# UFL.net
KiCad netlist of a schematic drawn in Altium Designer
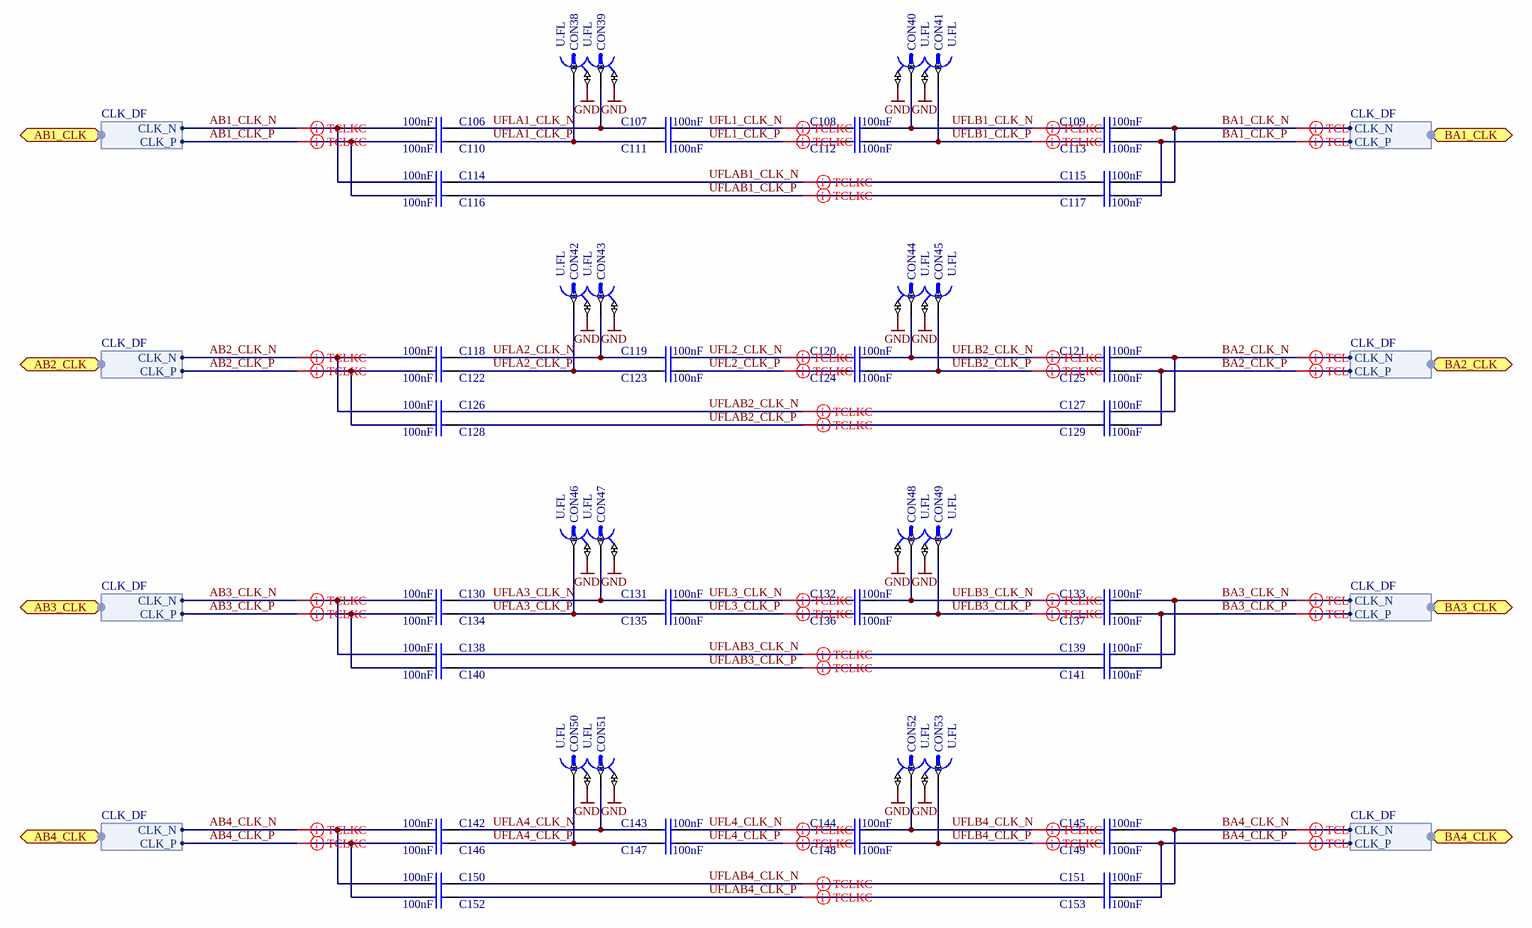
[diagram p0: UFL.SchDoc]

(export (version "E")
  (design (tool "Eeschema 10.0.6"))
  (components
    (comp (ref "C106")
      (value "100nF")
      (footprint "CAPC0603X33N")
      (description "Non-polarised capacitor")
      (fields
        (field (name "PART NUMBER") "CC0201_100NF_6.3V_10%_X5R")
        (field (name "VOLTAGE") "6.3V")
        (field (name "AUTHOR") "CERN DEM JLC")
      )
      (libsource (lib "Capacitors") (part "Capacitor - non polarized"))
    )
    (comp (ref "C107")
      (value "100nF")
      (footprint "CAPC0603X33N")
      (description "Non-polarised capacitor")
      (fields
        (field (name "PART NUMBER") "CC0201_100NF_6.3V_10%_X5R")
        (field (name "VOLTAGE") "6.3V")
        (field (name "AUTHOR") "CERN DEM JLC")
      )
      (libsource (lib "Capacitors") (part "Capacitor - non polarized"))
    )
    (comp (ref "C108")
      (value "100nF")
      (footprint "CAPC0603X33N")
      (description "Non-polarised capacitor")
      (fields
        (field (name "PART NUMBER") "CC0201_100NF_6.3V_10%_X5R")
        (field (name "VOLTAGE") "6.3V")
        (field (name "AUTHOR") "CERN DEM JLC")
      )
      (libsource (lib "Capacitors") (part "Capacitor - non polarized"))
    )
    (comp (ref "C109")
      (value "100nF")
      (footprint "CAPC0603X33N")
      (description "Non-polarised capacitor")
      (fields
        (field (name "PART NUMBER") "CC0201_100NF_6.3V_10%_X5R")
        (field (name "VOLTAGE") "6.3V")
        (field (name "AUTHOR") "CERN DEM JLC")
      )
      (libsource (lib "Capacitors") (part "Capacitor - non polarized"))
    )
    (comp (ref "C110")
      (value "100nF")
      (footprint "CAPC0603X33N")
      (description "Non-polarised capacitor")
      (fields
        (field (name "PART NUMBER") "CC0201_100NF_6.3V_10%_X5R")
        (field (name "VOLTAGE") "6.3V")
        (field (name "AUTHOR") "CERN DEM JLC")
      )
      (libsource (lib "Capacitors") (part "Capacitor - non polarized"))
    )
    (comp (ref "C111")
      (value "100nF")
      (footprint "CAPC0603X33N")
      (description "Non-polarised capacitor")
      (fields
        (field (name "PART NUMBER") "CC0201_100NF_6.3V_10%_X5R")
        (field (name "VOLTAGE") "6.3V")
        (field (name "AUTHOR") "CERN DEM JLC")
      )
      (libsource (lib "Capacitors") (part "Capacitor - non polarized"))
    )
    (comp (ref "C112")
      (value "100nF")
      (footprint "CAPC0603X33N")
      (description "Non-polarised capacitor")
      (fields
        (field (name "PART NUMBER") "CC0201_100NF_6.3V_10%_X5R")
        (field (name "VOLTAGE") "6.3V")
        (field (name "AUTHOR") "CERN DEM JLC")
      )
      (libsource (lib "Capacitors") (part "Capacitor - non polarized"))
    )
    (comp (ref "C113")
      (value "100nF")
      (footprint "CAPC0603X33N")
      (description "Non-polarised capacitor")
      (fields
        (field (name "PART NUMBER") "CC0201_100NF_6.3V_10%_X5R")
        (field (name "VOLTAGE") "6.3V")
        (field (name "AUTHOR") "CERN DEM JLC")
      )
      (libsource (lib "Capacitors") (part "Capacitor - non polarized"))
    )
    (comp (ref "C114")
      (value "100nF")
      (footprint "CAPC0603X33N")
      (description "Non-polarised capacitor")
      (fields
        (field (name "PART NUMBER") "CC0201_100NF_6.3V_10%_X5R")
        (field (name "VOLTAGE") "6.3V")
        (field (name "AUTHOR") "CERN DEM JLC")
      )
      (libsource (lib "Capacitors") (part "Capacitor - non polarized"))
    )
    (comp (ref "C115")
      (value "100nF")
      (footprint "CAPC0603X33N")
      (description "Non-polarised capacitor")
      (fields
        (field (name "PART NUMBER") "CC0201_100NF_6.3V_10%_X5R")
        (field (name "VOLTAGE") "6.3V")
        (field (name "AUTHOR") "CERN DEM JLC")
      )
      (libsource (lib "Capacitors") (part "Capacitor - non polarized"))
    )
    (comp (ref "C116")
      (value "100nF")
      (footprint "CAPC0603X33N")
      (description "Non-polarised capacitor")
      (fields
        (field (name "PART NUMBER") "CC0201_100NF_6.3V_10%_X5R")
        (field (name "VOLTAGE") "6.3V")
        (field (name "AUTHOR") "CERN DEM JLC")
      )
      (libsource (lib "Capacitors") (part "Capacitor - non polarized"))
    )
    (comp (ref "C117")
      (value "100nF")
      (footprint "CAPC0603X33N")
      (description "Non-polarised capacitor")
      (fields
        (field (name "PART NUMBER") "CC0201_100NF_6.3V_10%_X5R")
        (field (name "VOLTAGE") "6.3V")
        (field (name "AUTHOR") "CERN DEM JLC")
      )
      (libsource (lib "Capacitors") (part "Capacitor - non polarized"))
    )
    (comp (ref "C118")
      (value "100nF")
      (footprint "CAPC0603X33N")
      (description "Non-polarised capacitor")
      (fields
        (field (name "PART NUMBER") "CC0201_100NF_6.3V_10%_X5R")
        (field (name "VOLTAGE") "6.3V")
        (field (name "AUTHOR") "CERN DEM JLC")
      )
      (libsource (lib "Capacitors") (part "Capacitor - non polarized"))
    )
    (comp (ref "C119")
      (value "100nF")
      (footprint "CAPC0603X33N")
      (description "Non-polarised capacitor")
      (fields
        (field (name "PART NUMBER") "CC0201_100NF_6.3V_10%_X5R")
        (field (name "VOLTAGE") "6.3V")
        (field (name "AUTHOR") "CERN DEM JLC")
      )
      (libsource (lib "Capacitors") (part "Capacitor - non polarized"))
    )
    (comp (ref "C120")
      (value "100nF")
      (footprint "CAPC0603X33N")
      (description "Non-polarised capacitor")
      (fields
        (field (name "PART NUMBER") "CC0201_100NF_6.3V_10%_X5R")
        (field (name "VOLTAGE") "6.3V")
        (field (name "AUTHOR") "CERN DEM JLC")
      )
      (libsource (lib "Capacitors") (part "Capacitor - non polarized"))
    )
    (comp (ref "C121")
      (value "100nF")
      (footprint "CAPC0603X33N")
      (description "Non-polarised capacitor")
      (fields
        (field (name "PART NUMBER") "CC0201_100NF_6.3V_10%_X5R")
        (field (name "VOLTAGE") "6.3V")
        (field (name "AUTHOR") "CERN DEM JLC")
      )
      (libsource (lib "Capacitors") (part "Capacitor - non polarized"))
    )
    (comp (ref "C122")
      (value "100nF")
      (footprint "CAPC0603X33N")
      (description "Non-polarised capacitor")
      (fields
        (field (name "PART NUMBER") "CC0201_100NF_6.3V_10%_X5R")
        (field (name "VOLTAGE") "6.3V")
        (field (name "AUTHOR") "CERN DEM JLC")
      )
      (libsource (lib "Capacitors") (part "Capacitor - non polarized"))
    )
    (comp (ref "C123")
      (value "100nF")
      (footprint "CAPC0603X33N")
      (description "Non-polarised capacitor")
      (fields
        (field (name "PART NUMBER") "CC0201_100NF_6.3V_10%_X5R")
        (field (name "VOLTAGE") "6.3V")
        (field (name "AUTHOR") "CERN DEM JLC")
      )
      (libsource (lib "Capacitors") (part "Capacitor - non polarized"))
    )
    (comp (ref "C124")
      (value "100nF")
      (footprint "CAPC0603X33N")
      (description "Non-polarised capacitor")
      (fields
        (field (name "PART NUMBER") "CC0201_100NF_6.3V_10%_X5R")
        (field (name "VOLTAGE") "6.3V")
        (field (name "AUTHOR") "CERN DEM JLC")
      )
      (libsource (lib "Capacitors") (part "Capacitor - non polarized"))
    )
    (comp (ref "C125")
      (value "100nF")
      (footprint "CAPC0603X33N")
      (description "Non-polarised capacitor")
      (fields
        (field (name "PART NUMBER") "CC0201_100NF_6.3V_10%_X5R")
        (field (name "VOLTAGE") "6.3V")
        (field (name "AUTHOR") "CERN DEM JLC")
      )
      (libsource (lib "Capacitors") (part "Capacitor - non polarized"))
    )
    (comp (ref "C126")
      (value "100nF")
      (footprint "CAPC0603X33N")
      (description "Non-polarised capacitor")
      (fields
        (field (name "PART NUMBER") "CC0201_100NF_6.3V_10%_X5R")
        (field (name "VOLTAGE") "6.3V")
        (field (name "AUTHOR") "CERN DEM JLC")
      )
      (libsource (lib "Capacitors") (part "Capacitor - non polarized"))
    )
    (comp (ref "C127")
      (value "100nF")
      (footprint "CAPC0603X33N")
      (description "Non-polarised capacitor")
      (fields
        (field (name "PART NUMBER") "CC0201_100NF_6.3V_10%_X5R")
        (field (name "VOLTAGE") "6.3V")
        (field (name "AUTHOR") "CERN DEM JLC")
      )
      (libsource (lib "Capacitors") (part "Capacitor - non polarized"))
    )
    (comp (ref "C128")
      (value "100nF")
      (footprint "CAPC0603X33N")
      (description "Non-polarised capacitor")
      (fields
        (field (name "PART NUMBER") "CC0201_100NF_6.3V_10%_X5R")
        (field (name "VOLTAGE") "6.3V")
        (field (name "AUTHOR") "CERN DEM JLC")
      )
      (libsource (lib "Capacitors") (part "Capacitor - non polarized"))
    )
    (comp (ref "C129")
      (value "100nF")
      (footprint "CAPC0603X33N")
      (description "Non-polarised capacitor")
      (fields
        (field (name "PART NUMBER") "CC0201_100NF_6.3V_10%_X5R")
        (field (name "VOLTAGE") "6.3V")
        (field (name "AUTHOR") "CERN DEM JLC")
      )
      (libsource (lib "Capacitors") (part "Capacitor - non polarized"))
    )
    (comp (ref "C130")
      (value "100nF")
      (footprint "CAPC0603X33N")
      (description "Non-polarised capacitor")
      (fields
        (field (name "PART NUMBER") "CC0201_100NF_6.3V_10%_X5R")
        (field (name "VOLTAGE") "6.3V")
        (field (name "AUTHOR") "CERN DEM JLC")
      )
      (libsource (lib "Capacitors") (part "Capacitor - non polarized"))
    )
    (comp (ref "C131")
      (value "100nF")
      (footprint "CAPC0603X33N")
      (description "Non-polarised capacitor")
      (fields
        (field (name "PART NUMBER") "CC0201_100NF_6.3V_10%_X5R")
        (field (name "VOLTAGE") "6.3V")
        (field (name "AUTHOR") "CERN DEM JLC")
      )
      (libsource (lib "Capacitors") (part "Capacitor - non polarized"))
    )
    (comp (ref "C132")
      (value "100nF")
      (footprint "CAPC0603X33N")
      (description "Non-polarised capacitor")
      (fields
        (field (name "PART NUMBER") "CC0201_100NF_6.3V_10%_X5R")
        (field (name "VOLTAGE") "6.3V")
        (field (name "AUTHOR") "CERN DEM JLC")
      )
      (libsource (lib "Capacitors") (part "Capacitor - non polarized"))
    )
    (comp (ref "C133")
      (value "100nF")
      (footprint "CAPC0603X33N")
      (description "Non-polarised capacitor")
      (fields
        (field (name "PART NUMBER") "CC0201_100NF_6.3V_10%_X5R")
        (field (name "VOLTAGE") "6.3V")
        (field (name "AUTHOR") "CERN DEM JLC")
      )
      (libsource (lib "Capacitors") (part "Capacitor - non polarized"))
    )
    (comp (ref "C134")
      (value "100nF")
      (footprint "CAPC0603X33N")
      (description "Non-polarised capacitor")
      (fields
        (field (name "PART NUMBER") "CC0201_100NF_6.3V_10%_X5R")
        (field (name "VOLTAGE") "6.3V")
        (field (name "AUTHOR") "CERN DEM JLC")
      )
      (libsource (lib "Capacitors") (part "Capacitor - non polarized"))
    )
    (comp (ref "C135")
      (value "100nF")
      (footprint "CAPC0603X33N")
      (description "Non-polarised capacitor")
      (fields
        (field (name "PART NUMBER") "CC0201_100NF_6.3V_10%_X5R")
        (field (name "VOLTAGE") "6.3V")
        (field (name "AUTHOR") "CERN DEM JLC")
      )
      (libsource (lib "Capacitors") (part "Capacitor - non polarized"))
    )
    (comp (ref "C136")
      (value "100nF")
      (footprint "CAPC0603X33N")
      (description "Non-polarised capacitor")
      (fields
        (field (name "PART NUMBER") "CC0201_100NF_6.3V_10%_X5R")
        (field (name "VOLTAGE") "6.3V")
        (field (name "AUTHOR") "CERN DEM JLC")
      )
      (libsource (lib "Capacitors") (part "Capacitor - non polarized"))
    )
    (comp (ref "C137")
      (value "100nF")
      (footprint "CAPC0603X33N")
      (description "Non-polarised capacitor")
      (fields
        (field (name "PART NUMBER") "CC0201_100NF_6.3V_10%_X5R")
        (field (name "VOLTAGE") "6.3V")
        (field (name "AUTHOR") "CERN DEM JLC")
      )
      (libsource (lib "Capacitors") (part "Capacitor - non polarized"))
    )
    (comp (ref "C138")
      (value "100nF")
      (footprint "CAPC0603X33N")
      (description "Non-polarised capacitor")
      (fields
        (field (name "PART NUMBER") "CC0201_100NF_6.3V_10%_X5R")
        (field (name "VOLTAGE") "6.3V")
        (field (name "AUTHOR") "CERN DEM JLC")
      )
      (libsource (lib "Capacitors") (part "Capacitor - non polarized"))
    )
    (comp (ref "C139")
      (value "100nF")
      (footprint "CAPC0603X33N")
      (description "Non-polarised capacitor")
      (fields
        (field (name "PART NUMBER") "CC0201_100NF_6.3V_10%_X5R")
        (field (name "VOLTAGE") "6.3V")
        (field (name "AUTHOR") "CERN DEM JLC")
      )
      (libsource (lib "Capacitors") (part "Capacitor - non polarized"))
    )
    (comp (ref "C140")
      (value "100nF")
      (footprint "CAPC0603X33N")
      (description "Non-polarised capacitor")
      (fields
        (field (name "PART NUMBER") "CC0201_100NF_6.3V_10%_X5R")
        (field (name "VOLTAGE") "6.3V")
        (field (name "AUTHOR") "CERN DEM JLC")
      )
      (libsource (lib "Capacitors") (part "Capacitor - non polarized"))
    )
    (comp (ref "C141")
      (value "100nF")
      (footprint "CAPC0603X33N")
      (description "Non-polarised capacitor")
      (fields
        (field (name "PART NUMBER") "CC0201_100NF_6.3V_10%_X5R")
        (field (name "VOLTAGE") "6.3V")
        (field (name "AUTHOR") "CERN DEM JLC")
      )
      (libsource (lib "Capacitors") (part "Capacitor - non polarized"))
    )
    (comp (ref "C142")
      (value "100nF")
      (footprint "CAPC0603X33N")
      (description "Non-polarised capacitor")
      (fields
        (field (name "PART NUMBER") "CC0201_100NF_6.3V_10%_X5R")
        (field (name "VOLTAGE") "6.3V")
        (field (name "AUTHOR") "CERN DEM JLC")
      )
      (libsource (lib "Capacitors") (part "Capacitor - non polarized"))
    )
    (comp (ref "C143")
      (value "100nF")
      (footprint "CAPC0603X33N")
      (description "Non-polarised capacitor")
      (fields
        (field (name "PART NUMBER") "CC0201_100NF_6.3V_10%_X5R")
        (field (name "VOLTAGE") "6.3V")
        (field (name "AUTHOR") "CERN DEM JLC")
      )
      (libsource (lib "Capacitors") (part "Capacitor - non polarized"))
    )
    (comp (ref "C144")
      (value "100nF")
      (footprint "CAPC0603X33N")
      (description "Non-polarised capacitor")
      (fields
        (field (name "PART NUMBER") "CC0201_100NF_6.3V_10%_X5R")
        (field (name "VOLTAGE") "6.3V")
        (field (name "AUTHOR") "CERN DEM JLC")
      )
      (libsource (lib "Capacitors") (part "Capacitor - non polarized"))
    )
    (comp (ref "C145")
      (value "100nF")
      (footprint "CAPC0603X33N")
      (description "Non-polarised capacitor")
      (fields
        (field (name "PART NUMBER") "CC0201_100NF_6.3V_10%_X5R")
        (field (name "VOLTAGE") "6.3V")
        (field (name "AUTHOR") "CERN DEM JLC")
      )
      (libsource (lib "Capacitors") (part "Capacitor - non polarized"))
    )
    (comp (ref "C146")
      (value "100nF")
      (footprint "CAPC0603X33N")
      (description "Non-polarised capacitor")
      (fields
        (field (name "PART NUMBER") "CC0201_100NF_6.3V_10%_X5R")
        (field (name "VOLTAGE") "6.3V")
        (field (name "AUTHOR") "CERN DEM JLC")
      )
      (libsource (lib "Capacitors") (part "Capacitor - non polarized"))
    )
    (comp (ref "C147")
      (value "100nF")
      (footprint "CAPC0603X33N")
      (description "Non-polarised capacitor")
      (fields
        (field (name "PART NUMBER") "CC0201_100NF_6.3V_10%_X5R")
        (field (name "VOLTAGE") "6.3V")
        (field (name "AUTHOR") "CERN DEM JLC")
      )
      (libsource (lib "Capacitors") (part "Capacitor - non polarized"))
    )
    (comp (ref "C148")
      (value "100nF")
      (footprint "CAPC0603X33N")
      (description "Non-polarised capacitor")
      (fields
        (field (name "PART NUMBER") "CC0201_100NF_6.3V_10%_X5R")
        (field (name "VOLTAGE") "6.3V")
        (field (name "AUTHOR") "CERN DEM JLC")
      )
      (libsource (lib "Capacitors") (part "Capacitor - non polarized"))
    )
    (comp (ref "C149")
      (value "100nF")
      (footprint "CAPC0603X33N")
      (description "Non-polarised capacitor")
      (fields
        (field (name "PART NUMBER") "CC0201_100NF_6.3V_10%_X5R")
        (field (name "VOLTAGE") "6.3V")
        (field (name "AUTHOR") "CERN DEM JLC")
      )
      (libsource (lib "Capacitors") (part "Capacitor - non polarized"))
    )
    (comp (ref "C150")
      (value "100nF")
      (footprint "CAPC0603X33N")
      (description "Non-polarised capacitor")
      (fields
        (field (name "PART NUMBER") "CC0201_100NF_6.3V_10%_X5R")
        (field (name "VOLTAGE") "6.3V")
        (field (name "AUTHOR") "CERN DEM JLC")
      )
      (libsource (lib "Capacitors") (part "Capacitor - non polarized"))
    )
    (comp (ref "C151")
      (value "100nF")
      (footprint "CAPC0603X33N")
      (description "Non-polarised capacitor")
      (fields
        (field (name "PART NUMBER") "CC0201_100NF_6.3V_10%_X5R")
        (field (name "VOLTAGE") "6.3V")
        (field (name "AUTHOR") "CERN DEM JLC")
      )
      (libsource (lib "Capacitors") (part "Capacitor - non polarized"))
    )
    (comp (ref "C152")
      (value "100nF")
      (footprint "CAPC0603X33N")
      (description "Non-polarised capacitor")
      (fields
        (field (name "PART NUMBER") "CC0201_100NF_6.3V_10%_X5R")
        (field (name "VOLTAGE") "6.3V")
        (field (name "AUTHOR") "CERN DEM JLC")
      )
      (libsource (lib "Capacitors") (part "Capacitor - non polarized"))
    )
    (comp (ref "C153")
      (value "100nF")
      (footprint "CAPC0603X33N")
      (description "Non-polarised capacitor")
      (fields
        (field (name "PART NUMBER") "CC0201_100NF_6.3V_10%_X5R")
        (field (name "VOLTAGE") "6.3V")
        (field (name "AUTHOR") "CERN DEM JLC")
      )
      (libsource (lib "Capacitors") (part "Capacitor - non polarized"))
    )
    (comp (ref "CON38")
      (value "U.FL")
      (footprint "HIROSE_U.FL-R-SMT-1(10)")
      (fields
        (field (name "PART NUMBER") "HIROSE_U.FL-R-SMT-1(10)")
        (field (name "MANUFACTURER") "HIROSE (HRS)")
        (field (name "MANUFACTURER PART NUMBER") "U.FL-R-SMT-1(10)")
        (field (name "AUTHOR") "CERN DEM JLC")
      )
      (libsource (lib "Connectors") (part "Coax_1Male_1Shield"))
    )
    (comp (ref "CON39")
      (value "U.FL")
      (footprint "HIROSE_U.FL-R-SMT-1(10)")
      (fields
        (field (name "PART NUMBER") "HIROSE_U.FL-R-SMT-1(10)")
        (field (name "MANUFACTURER") "HIROSE (HRS)")
        (field (name "MANUFACTURER PART NUMBER") "U.FL-R-SMT-1(10)")
        (field (name "AUTHOR") "CERN DEM JLC")
      )
      (libsource (lib "Connectors") (part "Coax_1Male_1Shield"))
    )
    (comp (ref "CON40")
      (value "U.FL")
      (footprint "HIROSE_U.FL-R-SMT-1(10)")
      (fields
        (field (name "PART NUMBER") "HIROSE_U.FL-R-SMT-1(10)")
        (field (name "MANUFACTURER") "HIROSE (HRS)")
        (field (name "MANUFACTURER PART NUMBER") "U.FL-R-SMT-1(10)")
        (field (name "AUTHOR") "CERN DEM JLC")
      )
      (libsource (lib "") (part "Coax_1Male_1Shield_1"))
    )
    (comp (ref "CON41")
      (value "U.FL")
      (footprint "HIROSE_U.FL-R-SMT-1(10)")
      (fields
        (field (name "PART NUMBER") "HIROSE_U.FL-R-SMT-1(10)")
        (field (name "MANUFACTURER") "HIROSE (HRS)")
        (field (name "MANUFACTURER PART NUMBER") "U.FL-R-SMT-1(10)")
        (field (name "AUTHOR") "CERN DEM JLC")
      )
      (libsource (lib "") (part "Coax_1Male_1Shield_1"))
    )
    (comp (ref "CON42")
      (value "U.FL")
      (footprint "HIROSE_U.FL-R-SMT-1(10)")
      (fields
        (field (name "PART NUMBER") "HIROSE_U.FL-R-SMT-1(10)")
        (field (name "MANUFACTURER") "HIROSE (HRS)")
        (field (name "MANUFACTURER PART NUMBER") "U.FL-R-SMT-1(10)")
        (field (name "AUTHOR") "CERN DEM JLC")
      )
      (libsource (lib "Connectors") (part "Coax_1Male_1Shield"))
    )
    (comp (ref "CON43")
      (value "U.FL")
      (footprint "HIROSE_U.FL-R-SMT-1(10)")
      (fields
        (field (name "PART NUMBER") "HIROSE_U.FL-R-SMT-1(10)")
        (field (name "MANUFACTURER") "HIROSE (HRS)")
        (field (name "MANUFACTURER PART NUMBER") "U.FL-R-SMT-1(10)")
        (field (name "AUTHOR") "CERN DEM JLC")
      )
      (libsource (lib "Connectors") (part "Coax_1Male_1Shield"))
    )
    (comp (ref "CON44")
      (value "U.FL")
      (footprint "HIROSE_U.FL-R-SMT-1(10)")
      (fields
        (field (name "PART NUMBER") "HIROSE_U.FL-R-SMT-1(10)")
        (field (name "MANUFACTURER") "HIROSE (HRS)")
        (field (name "MANUFACTURER PART NUMBER") "U.FL-R-SMT-1(10)")
        (field (name "AUTHOR") "CERN DEM JLC")
      )
      (libsource (lib "") (part "Coax_1Male_1Shield_1"))
    )
    (comp (ref "CON45")
      (value "U.FL")
      (footprint "HIROSE_U.FL-R-SMT-1(10)")
      (fields
        (field (name "PART NUMBER") "HIROSE_U.FL-R-SMT-1(10)")
        (field (name "MANUFACTURER") "HIROSE (HRS)")
        (field (name "MANUFACTURER PART NUMBER") "U.FL-R-SMT-1(10)")
        (field (name "AUTHOR") "CERN DEM JLC")
      )
      (libsource (lib "") (part "Coax_1Male_1Shield_1"))
    )
    (comp (ref "CON46")
      (value "U.FL")
      (footprint "HIROSE_U.FL-R-SMT-1(10)")
      (fields
        (field (name "PART NUMBER") "HIROSE_U.FL-R-SMT-1(10)")
        (field (name "MANUFACTURER") "HIROSE (HRS)")
        (field (name "MANUFACTURER PART NUMBER") "U.FL-R-SMT-1(10)")
        (field (name "AUTHOR") "CERN DEM JLC")
      )
      (libsource (lib "Connectors") (part "Coax_1Male_1Shield"))
    )
    (comp (ref "CON47")
      (value "U.FL")
      (footprint "HIROSE_U.FL-R-SMT-1(10)")
      (fields
        (field (name "PART NUMBER") "HIROSE_U.FL-R-SMT-1(10)")
        (field (name "MANUFACTURER") "HIROSE (HRS)")
        (field (name "MANUFACTURER PART NUMBER") "U.FL-R-SMT-1(10)")
        (field (name "AUTHOR") "CERN DEM JLC")
      )
      (libsource (lib "Connectors") (part "Coax_1Male_1Shield"))
    )
    (comp (ref "CON48")
      (value "U.FL")
      (footprint "HIROSE_U.FL-R-SMT-1(10)")
      (fields
        (field (name "PART NUMBER") "HIROSE_U.FL-R-SMT-1(10)")
        (field (name "MANUFACTURER") "HIROSE (HRS)")
        (field (name "MANUFACTURER PART NUMBER") "U.FL-R-SMT-1(10)")
        (field (name "AUTHOR") "CERN DEM JLC")
      )
      (libsource (lib "") (part "Coax_1Male_1Shield_1"))
    )
    (comp (ref "CON49")
      (value "U.FL")
      (footprint "HIROSE_U.FL-R-SMT-1(10)")
      (fields
        (field (name "PART NUMBER") "HIROSE_U.FL-R-SMT-1(10)")
        (field (name "MANUFACTURER") "HIROSE (HRS)")
        (field (name "MANUFACTURER PART NUMBER") "U.FL-R-SMT-1(10)")
        (field (name "AUTHOR") "CERN DEM JLC")
      )
      (libsource (lib "") (part "Coax_1Male_1Shield_1"))
    )
    (comp (ref "CON50")
      (value "U.FL")
      (footprint "HIROSE_U.FL-R-SMT-1(10)")
      (fields
        (field (name "PART NUMBER") "HIROSE_U.FL-R-SMT-1(10)")
        (field (name "MANUFACTURER") "HIROSE (HRS)")
        (field (name "MANUFACTURER PART NUMBER") "U.FL-R-SMT-1(10)")
        (field (name "AUTHOR") "CERN DEM JLC")
      )
      (libsource (lib "Connectors") (part "Coax_1Male_1Shield"))
    )
    (comp (ref "CON51")
      (value "U.FL")
      (footprint "HIROSE_U.FL-R-SMT-1(10)")
      (fields
        (field (name "PART NUMBER") "HIROSE_U.FL-R-SMT-1(10)")
        (field (name "MANUFACTURER") "HIROSE (HRS)")
        (field (name "MANUFACTURER PART NUMBER") "U.FL-R-SMT-1(10)")
        (field (name "AUTHOR") "CERN DEM JLC")
      )
      (libsource (lib "Connectors") (part "Coax_1Male_1Shield"))
    )
    (comp (ref "CON52")
      (value "U.FL")
      (footprint "HIROSE_U.FL-R-SMT-1(10)")
      (fields
        (field (name "PART NUMBER") "HIROSE_U.FL-R-SMT-1(10)")
        (field (name "MANUFACTURER") "HIROSE (HRS)")
        (field (name "MANUFACTURER PART NUMBER") "U.FL-R-SMT-1(10)")
        (field (name "AUTHOR") "CERN DEM JLC")
      )
      (libsource (lib "") (part "Coax_1Male_1Shield_1"))
    )
    (comp (ref "CON53")
      (value "U.FL")
      (footprint "HIROSE_U.FL-R-SMT-1(10)")
      (fields
        (field (name "PART NUMBER") "HIROSE_U.FL-R-SMT-1(10)")
        (field (name "MANUFACTURER") "HIROSE (HRS)")
        (field (name "MANUFACTURER PART NUMBER") "U.FL-R-SMT-1(10)")
        (field (name "AUTHOR") "CERN DEM JLC")
      )
      (libsource (lib "") (part "Coax_1Male_1Shield_1"))
    )
  )
  (nets
    (net (code "2") (name "/AB1_CLK_N") (class "Default")
      (node (ref "C106") (pin "1") (pinfunction "1_1") (pintype "passive"))
      (node (ref "C114") (pin "1") (pinfunction "1_1") (pintype "passive"))
    )
    (net (code "3") (name "/AB1_CLK_P") (class "Default")
      (node (ref "C110") (pin "1") (pinfunction "1_1") (pintype "passive"))
      (node (ref "C116") (pin "1") (pinfunction "1_1") (pintype "passive"))
    )
    (net (code "4") (name "/AB2_CLK_N") (class "Default")
      (node (ref "C118") (pin "1") (pinfunction "1_1") (pintype "passive"))
      (node (ref "C126") (pin "1") (pinfunction "1_1") (pintype "passive"))
    )
    (net (code "5") (name "/AB2_CLK_P") (class "Default")
      (node (ref "C122") (pin "1") (pinfunction "1_1") (pintype "passive"))
      (node (ref "C128") (pin "1") (pinfunction "1_1") (pintype "passive"))
    )
    (net (code "6") (name "/AB3_CLK_N") (class "Default")
      (node (ref "C130") (pin "1") (pinfunction "1_1") (pintype "passive"))
      (node (ref "C138") (pin "1") (pinfunction "1_1") (pintype "passive"))
    )
    (net (code "7") (name "/AB3_CLK_P") (class "Default")
      (node (ref "C134") (pin "1") (pinfunction "1_1") (pintype "passive"))
      (node (ref "C140") (pin "1") (pinfunction "1_1") (pintype "passive"))
    )
    (net (code "8") (name "/AB4_CLK_N") (class "Default")
      (node (ref "C142") (pin "1") (pinfunction "1_1") (pintype "passive"))
      (node (ref "C150") (pin "1") (pinfunction "1_1") (pintype "passive"))
    )
    (net (code "9") (name "/AB4_CLK_P") (class "Default")
      (node (ref "C146") (pin "1") (pinfunction "1_1") (pintype "passive"))
      (node (ref "C152") (pin "1") (pinfunction "1_1") (pintype "passive"))
    )
    (net (code "10") (name "/BA1_CLK_N") (class "Default")
      (node (ref "C109") (pin "1") (pinfunction "1_1") (pintype "passive"))
      (node (ref "C115") (pin "1") (pinfunction "1_1") (pintype "passive"))
    )
    (net (code "11") (name "/BA1_CLK_P") (class "Default")
      (node (ref "C113") (pin "1") (pinfunction "1_1") (pintype "passive"))
      (node (ref "C117") (pin "1") (pinfunction "1_1") (pintype "passive"))
    )
    (net (code "12") (name "/BA2_CLK_N") (class "Default")
      (node (ref "C121") (pin "1") (pinfunction "1_1") (pintype "passive"))
      (node (ref "C127") (pin "1") (pinfunction "1_1") (pintype "passive"))
    )
    (net (code "13") (name "/BA2_CLK_P") (class "Default")
      (node (ref "C125") (pin "1") (pinfunction "1_1") (pintype "passive"))
      (node (ref "C129") (pin "1") (pinfunction "1_1") (pintype "passive"))
    )
    (net (code "14") (name "/BA3_CLK_N") (class "Default")
      (node (ref "C133") (pin "1") (pinfunction "1_1") (pintype "passive"))
      (node (ref "C139") (pin "1") (pinfunction "1_1") (pintype "passive"))
    )
    (net (code "15") (name "/BA3_CLK_P") (class "Default")
      (node (ref "C137") (pin "1") (pinfunction "1_1") (pintype "passive"))
      (node (ref "C141") (pin "1") (pinfunction "1_1") (pintype "passive"))
    )
    (net (code "16") (name "/BA4_CLK_N") (class "Default")
      (node (ref "C145") (pin "1") (pinfunction "1_1") (pintype "passive"))
      (node (ref "C151") (pin "1") (pinfunction "1_1") (pintype "passive"))
    )
    (net (code "17") (name "/BA4_CLK_P") (class "Default")
      (node (ref "C149") (pin "1") (pinfunction "1_1") (pintype "passive"))
      (node (ref "C153") (pin "1") (pinfunction "1_1") (pintype "passive"))
    )
    (net (code "18") (name "/UFL1_CLK_N") (class "Default")
      (node (ref "C107") (pin "1") (pinfunction "1_1") (pintype "passive"))
      (node (ref "C108") (pin "2") (pinfunction "2_2") (pintype "passive"))
    )
    (net (code "19") (name "/UFL1_CLK_P") (class "Default")
      (node (ref "C111") (pin "1") (pinfunction "1_1") (pintype "passive"))
      (node (ref "C112") (pin "2") (pinfunction "2_2") (pintype "passive"))
    )
    (net (code "20") (name "/UFL2_CLK_N") (class "Default")
      (node (ref "C119") (pin "1") (pinfunction "1_1") (pintype "passive"))
      (node (ref "C120") (pin "2") (pinfunction "2_2") (pintype "passive"))
    )
    (net (code "21") (name "/UFL2_CLK_P") (class "Default")
      (node (ref "C123") (pin "1") (pinfunction "1_1") (pintype "passive"))
      (node (ref "C124") (pin "2") (pinfunction "2_2") (pintype "passive"))
    )
    (net (code "22") (name "/UFL3_CLK_N") (class "Default")
      (node (ref "C131") (pin "1") (pinfunction "1_1") (pintype "passive"))
      (node (ref "C132") (pin "2") (pinfunction "2_2") (pintype "passive"))
    )
    (net (code "23") (name "/UFL3_CLK_P") (class "Default")
      (node (ref "C135") (pin "1") (pinfunction "1_1") (pintype "passive"))
      (node (ref "C136") (pin "2") (pinfunction "2_2") (pintype "passive"))
    )
    (net (code "24") (name "/UFL4_CLK_N") (class "Default")
      (node (ref "C143") (pin "1") (pinfunction "1_1") (pintype "passive"))
      (node (ref "C144") (pin "2") (pinfunction "2_2") (pintype "passive"))
    )
    (net (code "25") (name "/UFL4_CLK_P") (class "Default")
      (node (ref "C147") (pin "1") (pinfunction "1_1") (pintype "passive"))
      (node (ref "C148") (pin "2") (pinfunction "2_2") (pintype "passive"))
    )
    (net (code "26") (name "/UFLA1_CLK_N") (class "Default")
      (node (ref "C106") (pin "2") (pinfunction "2_2") (pintype "passive"))
      (node (ref "C107") (pin "2") (pinfunction "2_2") (pintype "passive"))
      (node (ref "CON39") (pin "1") (pinfunction "1_1") (pintype "bidirectional"))
    )
    (net (code "27") (name "/UFLA1_CLK_P") (class "Default")
      (node (ref "C110") (pin "2") (pinfunction "2_2") (pintype "passive"))
      (node (ref "C111") (pin "2") (pinfunction "2_2") (pintype "passive"))
      (node (ref "CON38") (pin "1") (pinfunction "1_1") (pintype "bidirectional"))
    )
    (net (code "28") (name "/UFLA2_CLK_N") (class "Default")
      (node (ref "C118") (pin "2") (pinfunction "2_2") (pintype "passive"))
      (node (ref "C119") (pin "2") (pinfunction "2_2") (pintype "passive"))
      (node (ref "CON43") (pin "1") (pinfunction "1_1") (pintype "bidirectional"))
    )
    (net (code "29") (name "/UFLA2_CLK_P") (class "Default")
      (node (ref "C122") (pin "2") (pinfunction "2_2") (pintype "passive"))
      (node (ref "C123") (pin "2") (pinfunction "2_2") (pintype "passive"))
      (node (ref "CON42") (pin "1") (pinfunction "1_1") (pintype "bidirectional"))
    )
    (net (code "30") (name "/UFLA3_CLK_N") (class "Default")
      (node (ref "C130") (pin "2") (pinfunction "2_2") (pintype "passive"))
      (node (ref "C131") (pin "2") (pinfunction "2_2") (pintype "passive"))
      (node (ref "CON47") (pin "1") (pinfunction "1_1") (pintype "bidirectional"))
    )
    (net (code "31") (name "/UFLA3_CLK_P") (class "Default")
      (node (ref "C134") (pin "2") (pinfunction "2_2") (pintype "passive"))
      (node (ref "C135") (pin "2") (pinfunction "2_2") (pintype "passive"))
      (node (ref "CON46") (pin "1") (pinfunction "1_1") (pintype "bidirectional"))
    )
    (net (code "32") (name "/UFLA4_CLK_N") (class "Default")
      (node (ref "C142") (pin "2") (pinfunction "2_2") (pintype "passive"))
      (node (ref "C143") (pin "2") (pinfunction "2_2") (pintype "passive"))
      (node (ref "CON51") (pin "1") (pinfunction "1_1") (pintype "bidirectional"))
    )
    (net (code "33") (name "/UFLA4_CLK_P") (class "Default")
      (node (ref "C146") (pin "2") (pinfunction "2_2") (pintype "passive"))
      (node (ref "C147") (pin "2") (pinfunction "2_2") (pintype "passive"))
      (node (ref "CON50") (pin "1") (pinfunction "1_1") (pintype "bidirectional"))
    )
    (net (code "34") (name "/UFLAB1_CLK_N") (class "Default")
      (node (ref "C114") (pin "2") (pinfunction "2_2") (pintype "passive"))
      (node (ref "C115") (pin "2") (pinfunction "2_2") (pintype "passive"))
    )
    (net (code "35") (name "/UFLAB1_CLK_P") (class "Default")
      (node (ref "C116") (pin "2") (pinfunction "2_2") (pintype "passive"))
      (node (ref "C117") (pin "2") (pinfunction "2_2") (pintype "passive"))
    )
    (net (code "36") (name "/UFLAB2_CLK_N") (class "Default")
      (node (ref "C126") (pin "2") (pinfunction "2_2") (pintype "passive"))
      (node (ref "C127") (pin "2") (pinfunction "2_2") (pintype "passive"))
    )
    (net (code "37") (name "/UFLAB2_CLK_P") (class "Default")
      (node (ref "C128") (pin "2") (pinfunction "2_2") (pintype "passive"))
      (node (ref "C129") (pin "2") (pinfunction "2_2") (pintype "passive"))
    )
    (net (code "38") (name "/UFLAB3_CLK_N") (class "Default")
      (node (ref "C138") (pin "2") (pinfunction "2_2") (pintype "passive"))
      (node (ref "C139") (pin "2") (pinfunction "2_2") (pintype "passive"))
    )
    (net (code "39") (name "/UFLAB3_CLK_P") (class "Default")
      (node (ref "C140") (pin "2") (pinfunction "2_2") (pintype "passive"))
      (node (ref "C141") (pin "2") (pinfunction "2_2") (pintype "passive"))
    )
    (net (code "40") (name "/UFLAB4_CLK_N") (class "Default")
      (node (ref "C150") (pin "2") (pinfunction "2_2") (pintype "passive"))
      (node (ref "C151") (pin "2") (pinfunction "2_2") (pintype "passive"))
    )
    (net (code "41") (name "/UFLAB4_CLK_P") (class "Default")
      (node (ref "C152") (pin "2") (pinfunction "2_2") (pintype "passive"))
      (node (ref "C153") (pin "2") (pinfunction "2_2") (pintype "passive"))
    )
    (net (code "42") (name "/UFLB1_CLK_N") (class "Default")
      (node (ref "C108") (pin "1") (pinfunction "1_1") (pintype "passive"))
      (node (ref "C109") (pin "2") (pinfunction "2_2") (pintype "passive"))
      (node (ref "CON40") (pin "1") (pinfunction "1_1") (pintype "bidirectional"))
    )
    (net (code "43") (name "/UFLB1_CLK_P") (class "Default")
      (node (ref "C112") (pin "1") (pinfunction "1_1") (pintype "passive"))
      (node (ref "C113") (pin "2") (pinfunction "2_2") (pintype "passive"))
      (node (ref "CON41") (pin "1") (pinfunction "1_1") (pintype "bidirectional"))
    )
    (net (code "44") (name "/UFLB2_CLK_N") (class "Default")
      (node (ref "C120") (pin "1") (pinfunction "1_1") (pintype "passive"))
      (node (ref "C121") (pin "2") (pinfunction "2_2") (pintype "passive"))
      (node (ref "CON44") (pin "1") (pinfunction "1_1") (pintype "bidirectional"))
    )
    (net (code "45") (name "/UFLB2_CLK_P") (class "Default")
      (node (ref "C124") (pin "1") (pinfunction "1_1") (pintype "passive"))
      (node (ref "C125") (pin "2") (pinfunction "2_2") (pintype "passive"))
      (node (ref "CON45") (pin "1") (pinfunction "1_1") (pintype "bidirectional"))
    )
    (net (code "46") (name "/UFLB3_CLK_N") (class "Default")
      (node (ref "C132") (pin "1") (pinfunction "1_1") (pintype "passive"))
      (node (ref "C133") (pin "2") (pinfunction "2_2") (pintype "passive"))
      (node (ref "CON48") (pin "1") (pinfunction "1_1") (pintype "bidirectional"))
    )
    (net (code "47") (name "/UFLB3_CLK_P") (class "Default")
      (node (ref "C136") (pin "1") (pinfunction "1_1") (pintype "passive"))
      (node (ref "C137") (pin "2") (pinfunction "2_2") (pintype "passive"))
      (node (ref "CON49") (pin "1") (pinfunction "1_1") (pintype "bidirectional"))
    )
    (net (code "48") (name "/UFLB4_CLK_N") (class "Default")
      (node (ref "C144") (pin "1") (pinfunction "1_1") (pintype "passive"))
      (node (ref "C145") (pin "2") (pinfunction "2_2") (pintype "passive"))
      (node (ref "CON52") (pin "1") (pinfunction "1_1") (pintype "bidirectional"))
    )
    (net (code "49") (name "/UFLB4_CLK_P") (class "Default")
      (node (ref "C148") (pin "1") (pinfunction "1_1") (pintype "passive"))
      (node (ref "C149") (pin "2") (pinfunction "2_2") (pintype "passive"))
      (node (ref "CON53") (pin "1") (pinfunction "1_1") (pintype "bidirectional"))
    )
    (net (code "51") (name "GND") (class "Default")
      (node (ref "CON38") (pin "2") (pinfunction "2_2") (pintype "bidirectional"))
      (node (ref "CON39") (pin "2") (pinfunction "2_2") (pintype "bidirectional"))
      (node (ref "CON40") (pin "2") (pinfunction "2_2") (pintype "bidirectional"))
      (node (ref "CON41") (pin "2") (pinfunction "2_2") (pintype "bidirectional"))
      (node (ref "CON42") (pin "2") (pinfunction "2_2") (pintype "bidirectional"))
      (node (ref "CON43") (pin "2") (pinfunction "2_2") (pintype "bidirectional"))
      (node (ref "CON44") (pin "2") (pinfunction "2_2") (pintype "bidirectional"))
      (node (ref "CON45") (pin "2") (pinfunction "2_2") (pintype "bidirectional"))
      (node (ref "CON46") (pin "2") (pinfunction "2_2") (pintype "bidirectional"))
      (node (ref "CON47") (pin "2") (pinfunction "2_2") (pintype "bidirectional"))
      (node (ref "CON48") (pin "2") (pinfunction "2_2") (pintype "bidirectional"))
      (node (ref "CON49") (pin "2") (pinfunction "2_2") (pintype "bidirectional"))
      (node (ref "CON50") (pin "2") (pinfunction "2_2") (pintype "bidirectional"))
      (node (ref "CON51") (pin "2") (pinfunction "2_2") (pintype "bidirectional"))
      (node (ref "CON52") (pin "2") (pinfunction "2_2") (pintype "bidirectional"))
      (node (ref "CON53") (pin "2") (pinfunction "2_2") (pintype "bidirectional"))
    )
  )
)
